# STorM32_NT_imu_module_v008_mini.net
KiCad netlist of a schematic drawn in EAGLE
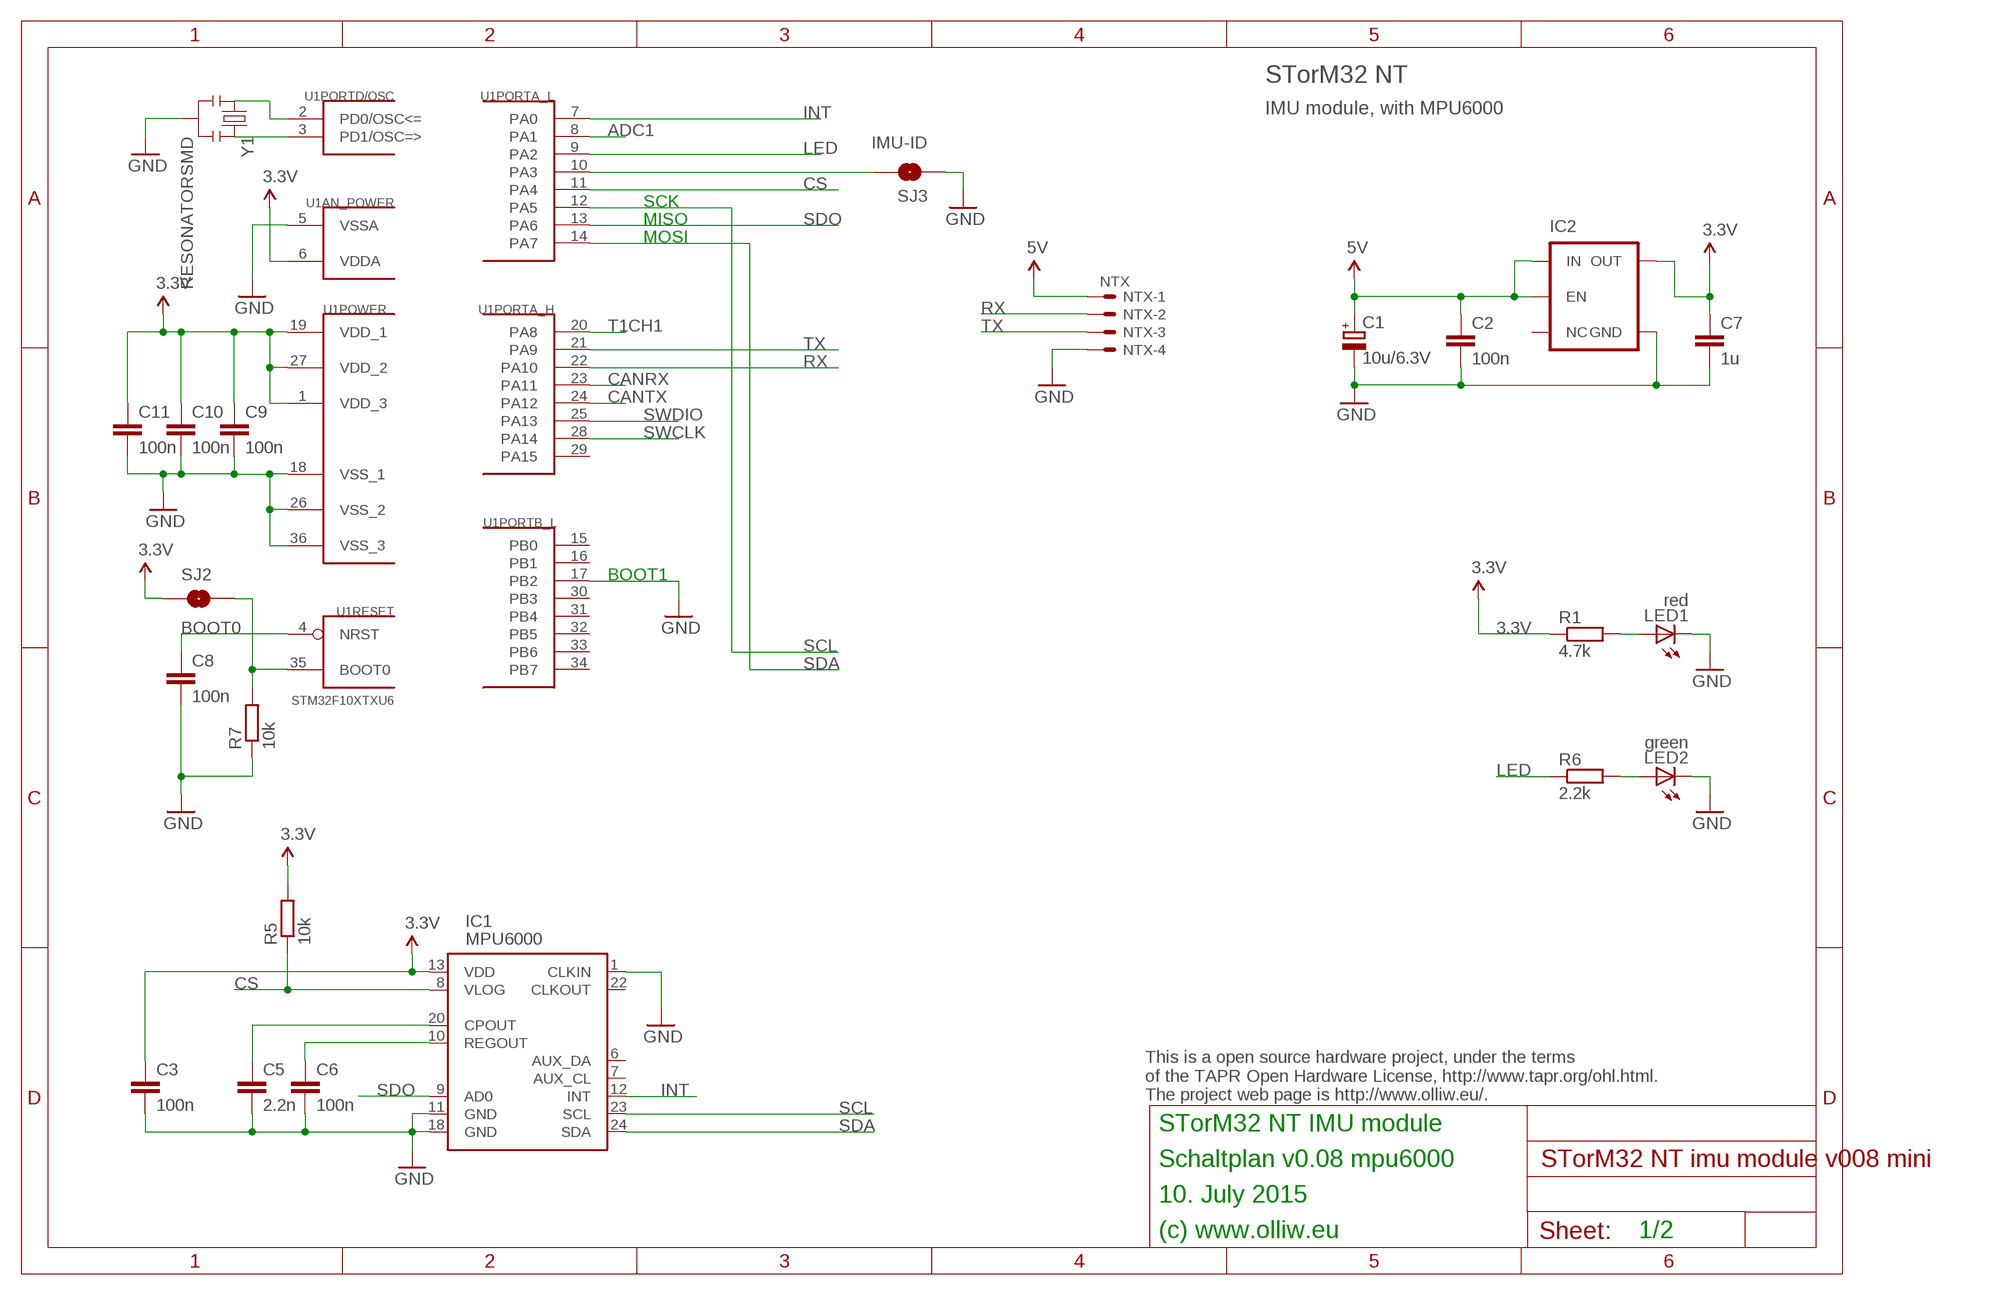
[diagram p0: schematic, sheet 1]

(export (version "E")
  (design (tool "Eeschema 10.0.6"))
  (components
    (comp (ref "C1")
      (value "10u/6.3V")
      (footprint "eagle-import:SMC_A")
      (libsource (lib "eagle-import") (part "CPOL-EUSMCA"))
    )
    (comp (ref "C2")
      (value "100n")
      (footprint "eagle-import:C0402")
      (libsource (lib "eagle-import") (part "C-EUC0402"))
    )
    (comp (ref "C3")
      (value "100n")
      (footprint "eagle-import:C0402")
      (libsource (lib "eagle-import") (part "C-EUC0402"))
    )
    (comp (ref "C5")
      (value "2.2n")
      (footprint "eagle-import:C0402")
      (libsource (lib "eagle-import") (part "C-EUC0402"))
    )
    (comp (ref "C6")
      (value "100n")
      (footprint "eagle-import:C0402")
      (libsource (lib "eagle-import") (part "C-EUC0402"))
    )
    (comp (ref "C7")
      (value "1u")
      (footprint "eagle-import:C0402")
      (libsource (lib "eagle-import") (part "C-EUC0402"))
    )
    (comp (ref "C8")
      (value "100n")
      (footprint "eagle-import:C0402")
      (libsource (lib "eagle-import") (part "C-EUC0402"))
    )
    (comp (ref "C9")
      (value "100n")
      (footprint "eagle-import:C0402")
      (libsource (lib "eagle-import") (part "C-EUC0402"))
    )
    (comp (ref "C10")
      (value "100n")
      (footprint "eagle-import:C0402")
      (libsource (lib "eagle-import") (part "C-EUC0402"))
    )
    (comp (ref "C11")
      (value "100n")
      (footprint "eagle-import:C0402")
      (libsource (lib "eagle-import") (part "C-EUC0402"))
    )
    (comp (ref "IC1")
      (value "MPU6000")
      (footprint "eagle-import:QFN-24")
      (libsource (lib "eagle-import") (part "IMU3000"))
    )
    (comp (ref "IC2")
      (value "V_REG_TPS76433SOT23-5")
      (footprint "eagle-import:SOT23-5")
      (libsource (lib "eagle-import") (part "V_REG_TPS76433SOT23-5"))
    )
    (comp (ref "LED1")
      (value "red")
      (footprint "eagle-import:CHIPLED_0603")
      (libsource (lib "eagle-import") (part "LEDCHIPLED_0603"))
    )
    (comp (ref "LED2")
      (value "green")
      (footprint "eagle-import:CHIPLED_0603")
      (libsource (lib "eagle-import") (part "LEDCHIPLED_0603"))
    )
    (comp (ref "NTX")
      (value "NTX")
      (footprint "eagle-import:SM04B-SRSS-TB")
      (libsource (lib "eagle-import") (part "?M04B-SRSS-TBS"))
    )
    (comp (ref "R1")
      (value "4.7k")
      (footprint "eagle-import:R0402")
      (libsource (lib "eagle-import") (part "R-EU_R0402"))
    )
    (comp (ref "R5")
      (value "10k")
      (footprint "eagle-import:R0402")
      (libsource (lib "eagle-import") (part "R-EU_R0402"))
    )
    (comp (ref "R6")
      (value "2.2k")
      (footprint "eagle-import:R0402")
      (libsource (lib "eagle-import") (part "R-EU_R0402"))
    )
    (comp (ref "R7")
      (value "10k")
      (footprint "eagle-import:R0402")
      (libsource (lib "eagle-import") (part "R-EU_R0402"))
    )
    (comp (ref "SJ2")
      (value "BOOT0")
      (footprint "eagle-import:SJ_2S-NO")
      (libsource (lib "eagle-import") (part "SOLDERJUMPERNO"))
    )
    (comp (ref "SJ3")
      (value "IMU-ID")
      (footprint "eagle-import:SJ_2S-NO")
      (libsource (lib "eagle-import") (part "SOLDERJUMPERNO"))
    )
    (comp (ref "U1")
      (value "STM32F10XTXU6")
      (footprint "eagle-import:VFQFPN36")
      (libsource (lib "eagle-import") (part "STM32F10XTXU6"))
    )
    (comp (ref "Y1")
      (value "RESONATORSMD")
      (footprint "eagle-import:RESONATOR-SMD")
      (libsource (lib "eagle-import") (part "RESONATORSMD"))
    )
  )
  (nets
    (net (code "1") (name "/ADC1") (class "Default")
      (node (ref "U1") (pin "8") (pinfunction "PA1_8") (pintype "bidirectional"))
    )
    (net (code "2") (name "/CANRX") (class "Default")
      (node (ref "U1") (pin "23") (pinfunction "PA11_23") (pintype "bidirectional"))
    )
    (net (code "3") (name "/CANTX") (class "Default")
      (node (ref "U1") (pin "24") (pinfunction "PA12_24") (pintype "bidirectional"))
    )
    (net (code "4") (name "/CS") (class "Default")
      (node (ref "IC1") (pin "8") (pinfunction "VLOG_8") (pintype "bidirectional"))
      (node (ref "R5") (pin "1") (pinfunction "1_1") (pintype "passive"))
      (node (ref "U1") (pin "11") (pinfunction "PA4_11") (pintype "bidirectional"))
    )
    (net (code "5") (name "/INT") (class "Default")
      (node (ref "IC1") (pin "12") (pinfunction "INT_12") (pintype "bidirectional"))
      (node (ref "U1") (pin "7") (pinfunction "PA0_7") (pintype "bidirectional"))
    )
    (net (code "6") (name "/LED") (class "Default")
      (node (ref "R6") (pin "1") (pinfunction "1_1") (pintype "passive"))
      (node (ref "U1") (pin "9") (pinfunction "PA2_9") (pintype "bidirectional"))
    )
    (net (code "7") (name "/RX") (class "Default")
      (node (ref "NTX") (pin "2") (pinfunction "S_2") (pintype "passive"))
      (node (ref "U1") (pin "22") (pinfunction "PA10_22") (pintype "bidirectional"))
    )
    (net (code "8") (name "/SCL") (class "Default")
      (node (ref "IC1") (pin "23") (pinfunction "SCL_23") (pintype "bidirectional"))
      (node (ref "U1") (pin "12") (pinfunction "PA5_12") (pintype "bidirectional"))
    )
    (net (code "9") (name "/SDA") (class "Default")
      (node (ref "IC1") (pin "24") (pinfunction "SDA_24") (pintype "bidirectional"))
      (node (ref "U1") (pin "14") (pinfunction "PA7_14") (pintype "bidirectional"))
    )
    (net (code "10") (name "/SDO") (class "Default")
      (node (ref "IC1") (pin "9") (pinfunction "AD0_9") (pintype "bidirectional"))
      (node (ref "U1") (pin "13") (pinfunction "PA6_13") (pintype "bidirectional"))
    )
    (net (code "11") (name "/SWCLK") (class "Default")
      (node (ref "U1") (pin "28") (pinfunction "PA14_28") (pintype "bidirectional"))
    )
    (net (code "12") (name "/SWDIO") (class "Default")
      (node (ref "U1") (pin "25") (pinfunction "PA13_25") (pintype "bidirectional"))
    )
    (net (code "13") (name "/T1CH1") (class "Default")
      (node (ref "U1") (pin "20") (pinfunction "PA8_20") (pintype "bidirectional"))
    )
    (net (code "14") (name "/TX") (class "Default")
      (node (ref "NTX") (pin "3") (pinfunction "S_3") (pintype "passive"))
      (node (ref "U1") (pin "21") (pinfunction "PA9_21") (pintype "bidirectional"))
    )
    (net (code "15") (name "3.3V") (class "Default")
      (node (ref "C10") (pin "1") (pinfunction "1_1") (pintype "passive"))
      (node (ref "C11") (pin "1") (pinfunction "1_1") (pintype "passive"))
      (node (ref "C3") (pin "1") (pinfunction "1_1") (pintype "passive"))
      (node (ref "C7") (pin "1") (pinfunction "1_1") (pintype "passive"))
      (node (ref "C9") (pin "1") (pinfunction "1_1") (pintype "passive"))
      (node (ref "IC1") (pin "13") (pinfunction "VDD_13") (pintype "bidirectional"))
      (node (ref "IC2") (pin "5") (pinfunction "OUT_5") (pintype "passive"))
      (node (ref "R1") (pin "1") (pinfunction "1_1") (pintype "passive"))
      (node (ref "R5") (pin "2") (pinfunction "2_2") (pintype "passive"))
      (node (ref "SJ2") (pin "1") (pinfunction "1_1") (pintype "passive"))
      (node (ref "U1") (pin "1") (pinfunction "VDD_3_1") (pintype "power_in"))
      (node (ref "U1") (pin "19") (pinfunction "VDD_1_19") (pintype "power_in"))
      (node (ref "U1") (pin "27") (pinfunction "VDD_2_27") (pintype "power_in"))
      (node (ref "U1") (pin "6") (pinfunction "VDDA_6") (pintype "power_in"))
    )
    (net (code "16") (name "5V") (class "Default")
      (node (ref "C1") (pin "+") (pinfunction "+_+") (pintype "passive"))
      (node (ref "C2") (pin "1") (pinfunction "1_1") (pintype "passive"))
      (node (ref "IC2") (pin "1") (pinfunction "IN_1") (pintype "input"))
      (node (ref "IC2") (pin "3") (pinfunction "EN_3") (pintype "input"))
      (node (ref "NTX") (pin "1") (pinfunction "S_1") (pintype "passive"))
    )
    (net (code "17") (name "GND") (class "Default")
      (node (ref "C1") (pin "-") (pinfunction "-_-") (pintype "passive"))
      (node (ref "C10") (pin "2") (pinfunction "2_2") (pintype "passive"))
      (node (ref "C11") (pin "2") (pinfunction "2_2") (pintype "passive"))
      (node (ref "C2") (pin "2") (pinfunction "2_2") (pintype "passive"))
      (node (ref "C3") (pin "2") (pinfunction "2_2") (pintype "passive"))
      (node (ref "C5") (pin "2") (pinfunction "2_2") (pintype "passive"))
      (node (ref "C6") (pin "2") (pinfunction "2_2") (pintype "passive"))
      (node (ref "C7") (pin "2") (pinfunction "2_2") (pintype "passive"))
      (node (ref "C8") (pin "2") (pinfunction "2_2") (pintype "passive"))
      (node (ref "C9") (pin "2") (pinfunction "2_2") (pintype "passive"))
      (node (ref "IC1") (pin "1") (pinfunction "CLKIN_1") (pintype "bidirectional"))
      (node (ref "IC1") (pin "11") (pinfunction "GND_11") (pintype "bidirectional"))
      (node (ref "IC1") (pin "18") (pinfunction "GND_18") (pintype "bidirectional"))
      (node (ref "IC2") (pin "2") (pinfunction "GND_2") (pintype "input"))
      (node (ref "LED1") (pin "C") (pinfunction "C_C") (pintype "passive"))
      (node (ref "LED2") (pin "C") (pinfunction "C_C") (pintype "passive"))
      (node (ref "NTX") (pin "4") (pinfunction "S_4") (pintype "passive"))
      (node (ref "R7") (pin "1") (pinfunction "1_1") (pintype "passive"))
      (node (ref "SJ3") (pin "1") (pinfunction "1_1") (pintype "passive"))
      (node (ref "U1") (pin "17") (pinfunction "PB2_17") (pintype "bidirectional"))
      (node (ref "U1") (pin "18") (pinfunction "VSS_1_18") (pintype "power_in"))
      (node (ref "U1") (pin "26") (pinfunction "VSS_2_26") (pintype "power_in"))
      (node (ref "U1") (pin "36") (pinfunction "VSS_3_36") (pintype "power_in"))
      (node (ref "U1") (pin "5") (pinfunction "VSSA_5") (pintype "power_in"))
      (node (ref "Y1") (pin "2") (pinfunction "2_2") (pintype "passive"))
    )
    (net (code "18") (name "Net-(IC1-CPOUT)") (class "Default")
      (node (ref "C5") (pin "1") (pinfunction "1_1") (pintype "passive"))
      (node (ref "IC1") (pin "20") (pinfunction "CPOUT_20") (pintype "bidirectional"))
    )
    (net (code "19") (name "Net-(IC1-REGOUT)") (class "Default")
      (node (ref "C6") (pin "1") (pinfunction "1_1") (pintype "passive"))
      (node (ref "IC1") (pin "10") (pinfunction "REGOUT_10") (pintype "bidirectional"))
    )
    (net (code "20") (name "Net-(LED1-PadA)") (class "Default")
      (node (ref "LED1") (pin "A") (pinfunction "A_A") (pintype "passive"))
      (node (ref "R1") (pin "2") (pinfunction "2_2") (pintype "passive"))
    )
    (net (code "21") (name "Net-(LED2-PadA)") (class "Default")
      (node (ref "LED2") (pin "A") (pinfunction "A_A") (pintype "passive"))
      (node (ref "R6") (pin "2") (pinfunction "2_2") (pintype "passive"))
    )
    (net (code "22") (name "Net-(U1C-PA3)") (class "Default")
      (node (ref "SJ3") (pin "2") (pinfunction "2_2") (pintype "passive"))
      (node (ref "U1") (pin "10") (pinfunction "PA3_10") (pintype "bidirectional"))
    )
    (net (code "23") (name "Net-(U1E-PD0{slash}OSC<=)") (class "Default")
      (node (ref "U1") (pin "2") (pinfunction "PD0/OSC<=_2") (pintype "bidirectional"))
      (node (ref "Y1") (pin "1") (pinfunction "1_1") (pintype "passive"))
    )
    (net (code "24") (name "Net-(U1E-PD1{slash}OSC=>)") (class "Default")
      (node (ref "U1") (pin "3") (pinfunction "PD1/OSC=>_3") (pintype "bidirectional"))
      (node (ref "Y1") (pin "3") (pinfunction "3_3") (pintype "passive"))
    )
    (net (code "25") (name "Net-(U1G-BOOT0)") (class "Default")
      (node (ref "R7") (pin "2") (pinfunction "2_2") (pintype "passive"))
      (node (ref "SJ2") (pin "2") (pinfunction "2_2") (pintype "passive"))
      (node (ref "U1") (pin "35") (pinfunction "BOOT0_35") (pintype "input"))
    )
    (net (code "26") (name "Net-(U1G-NRST)") (class "Default")
      (node (ref "C8") (pin "1") (pinfunction "1_1") (pintype "passive"))
      (node (ref "U1") (pin "4") (pinfunction "NRST_4") (pintype "input"))
    )
    (net (code "27") (name "unconnected-(IC1-AUX_CL-Pad7)") (class "Default")
      (node (ref "IC1") (pin "7") (pinfunction "AUX_CL_7") (pintype "bidirectional"))
    )
    (net (code "28") (name "unconnected-(IC1-AUX_DA-Pad6)") (class "Default")
      (node (ref "IC1") (pin "6") (pinfunction "AUX_DA_6") (pintype "bidirectional"))
    )
    (net (code "29") (name "unconnected-(IC1-CLKOUT-Pad22)") (class "Default")
      (node (ref "IC1") (pin "22") (pinfunction "CLKOUT_22") (pintype "bidirectional"))
    )
    (net (code "30") (name "unconnected-(IC2-NC-Pad4)") (class "Default")
      (node (ref "IC2") (pin "4") (pinfunction "NC_4") (pintype "input"))
    )
    (net (code "31") (name "unconnected-(U1B-PA15-Pad29)") (class "Default")
      (node (ref "U1") (pin "29") (pinfunction "PA15_29") (pintype "bidirectional"))
    )
    (net (code "32") (name "unconnected-(U1D-PB0-Pad15)") (class "Default")
      (node (ref "U1") (pin "15") (pinfunction "PB0_15") (pintype "bidirectional"))
    )
    (net (code "33") (name "unconnected-(U1D-PB1-Pad16)") (class "Default")
      (node (ref "U1") (pin "16") (pinfunction "PB1_16") (pintype "bidirectional"))
    )
    (net (code "34") (name "unconnected-(U1D-PB3-Pad30)") (class "Default")
      (node (ref "U1") (pin "30") (pinfunction "PB3_30") (pintype "bidirectional"))
    )
    (net (code "35") (name "unconnected-(U1D-PB4-Pad31)") (class "Default")
      (node (ref "U1") (pin "31") (pinfunction "PB4_31") (pintype "bidirectional"))
    )
    (net (code "36") (name "unconnected-(U1D-PB5-Pad32)") (class "Default")
      (node (ref "U1") (pin "32") (pinfunction "PB5_32") (pintype "bidirectional"))
    )
    (net (code "37") (name "unconnected-(U1D-PB6-Pad33)") (class "Default")
      (node (ref "U1") (pin "33") (pinfunction "PB6_33") (pintype "bidirectional"))
    )
    (net (code "38") (name "unconnected-(U1D-PB7-Pad34)") (class "Default")
      (node (ref "U1") (pin "34") (pinfunction "PB7_34") (pintype "bidirectional"))
    )
  )
)
